# txb0108.net
KiCad netlist of a schematic drawn in EAGLE
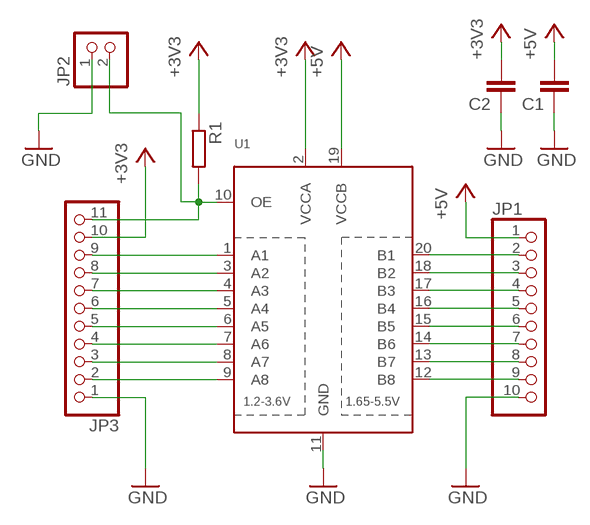
[diagram p0: schematic, sheet 1]

(export (version "E")
  (design (tool "Eeschema 10.0.6"))
  (components
    (comp (ref "C1")
      (value "C-EUC0805K")
      (footprint "eagle-import:C0805K")
      (libsource (lib "eagle-import") (part "C-EUC0805K"))
    )
    (comp (ref "C2")
      (value "C-EUC1206")
      (footprint "eagle-import:C1206")
      (libsource (lib "eagle-import") (part "C-EUC1206"))
    )
    (comp (ref "JP1")
      (value "PINHD-1X10")
      (footprint "eagle-import:1X10")
      (libsource (lib "eagle-import") (part "PINHD-1X10"))
    )
    (comp (ref "JP2")
      (value "PINHD-1X2")
      (footprint "eagle-import:1X02")
      (libsource (lib "eagle-import") (part "PINHD-1X2"))
    )
    (comp (ref "JP3")
      (value "PINHD-1X11")
      (footprint "eagle-import:1X11")
      (libsource (lib "eagle-import") (part "PINHD-1X11"))
    )
    (comp (ref "R1")
      (value "R-EU_M0805")
      (footprint "eagle-import:M0805")
      (libsource (lib "eagle-import") (part "R-EU_M0805"))
    )
    (comp (ref "U1")
      (value "TXB0108PWR")
      (footprint "eagle-import:TSSOP20")
      (libsource (lib "eagle-import") (part "TXB0108PWR"))
    )
  )
  (nets
    (net (code "1") (name "+3V3") (class "Default")
      (node (ref "C2") (pin "2") (pinfunction "2_2") (pintype "passive"))
      (node (ref "JP3") (pin "10") (pinfunction "10_10") (pintype "passive"))
      (node (ref "R1") (pin "1") (pinfunction "1_1") (pintype "passive"))
      (node (ref "U1") (pin "2") (pinfunction "VCCA_2") (pintype "bidirectional"))
    )
    (net (code "2") (name "+5V") (class "Default")
      (node (ref "C1") (pin "2") (pinfunction "2_2") (pintype "passive"))
      (node (ref "JP1") (pin "1") (pinfunction "1_1") (pintype "passive"))
      (node (ref "U1") (pin "19") (pinfunction "VCCB_19") (pintype "bidirectional"))
    )
    (net (code "3") (name "GND") (class "Default")
      (node (ref "C1") (pin "1") (pinfunction "1_1") (pintype "passive"))
      (node (ref "C2") (pin "1") (pinfunction "1_1") (pintype "passive"))
      (node (ref "JP1") (pin "10") (pinfunction "10_10") (pintype "passive"))
      (node (ref "JP2") (pin "1") (pinfunction "1_1") (pintype "passive"))
      (node (ref "JP3") (pin "1") (pinfunction "1_1") (pintype "passive"))
      (node (ref "U1") (pin "11") (pinfunction "GND_11") (pintype "bidirectional"))
    )
    (net (code "4") (name "Net-(U1-A1)") (class "Default")
      (node (ref "JP3") (pin "9") (pinfunction "9_9") (pintype "passive"))
      (node (ref "U1") (pin "1") (pinfunction "A1_1") (pintype "bidirectional"))
    )
    (net (code "5") (name "Net-(U1-A2)") (class "Default")
      (node (ref "JP3") (pin "8") (pinfunction "8_8") (pintype "passive"))
      (node (ref "U1") (pin "3") (pinfunction "A2_3") (pintype "bidirectional"))
    )
    (net (code "6") (name "Net-(U1-A3)") (class "Default")
      (node (ref "JP3") (pin "7") (pinfunction "7_7") (pintype "passive"))
      (node (ref "U1") (pin "4") (pinfunction "A3_4") (pintype "bidirectional"))
    )
    (net (code "7") (name "Net-(U1-A4)") (class "Default")
      (node (ref "JP3") (pin "6") (pinfunction "6_6") (pintype "passive"))
      (node (ref "U1") (pin "5") (pinfunction "A4_5") (pintype "bidirectional"))
    )
    (net (code "8") (name "Net-(U1-A5)") (class "Default")
      (node (ref "JP3") (pin "5") (pinfunction "5_5") (pintype "passive"))
      (node (ref "U1") (pin "6") (pinfunction "A5_6") (pintype "bidirectional"))
    )
    (net (code "9") (name "Net-(U1-A6)") (class "Default")
      (node (ref "JP3") (pin "4") (pinfunction "4_4") (pintype "passive"))
      (node (ref "U1") (pin "7") (pinfunction "A6_7") (pintype "bidirectional"))
    )
    (net (code "10") (name "Net-(U1-A7)") (class "Default")
      (node (ref "JP3") (pin "3") (pinfunction "3_3") (pintype "passive"))
      (node (ref "U1") (pin "8") (pinfunction "A7_8") (pintype "bidirectional"))
    )
    (net (code "11") (name "Net-(U1-A8)") (class "Default")
      (node (ref "JP3") (pin "2") (pinfunction "2_2") (pintype "passive"))
      (node (ref "U1") (pin "9") (pinfunction "A8_9") (pintype "bidirectional"))
    )
    (net (code "12") (name "Net-(U1-B1)") (class "Default")
      (node (ref "JP1") (pin "2") (pinfunction "2_2") (pintype "passive"))
      (node (ref "U1") (pin "20") (pinfunction "B1_20") (pintype "bidirectional"))
    )
    (net (code "13") (name "Net-(U1-B2)") (class "Default")
      (node (ref "JP1") (pin "3") (pinfunction "3_3") (pintype "passive"))
      (node (ref "U1") (pin "18") (pinfunction "B2_18") (pintype "bidirectional"))
    )
    (net (code "14") (name "Net-(U1-B3)") (class "Default")
      (node (ref "JP1") (pin "4") (pinfunction "4_4") (pintype "passive"))
      (node (ref "U1") (pin "17") (pinfunction "B3_17") (pintype "bidirectional"))
    )
    (net (code "15") (name "Net-(U1-B4)") (class "Default")
      (node (ref "JP1") (pin "5") (pinfunction "5_5") (pintype "passive"))
      (node (ref "U1") (pin "16") (pinfunction "B4_16") (pintype "bidirectional"))
    )
    (net (code "16") (name "Net-(U1-B5)") (class "Default")
      (node (ref "JP1") (pin "6") (pinfunction "6_6") (pintype "passive"))
      (node (ref "U1") (pin "15") (pinfunction "B5_15") (pintype "bidirectional"))
    )
    (net (code "17") (name "Net-(U1-B6)") (class "Default")
      (node (ref "JP1") (pin "7") (pinfunction "7_7") (pintype "passive"))
      (node (ref "U1") (pin "14") (pinfunction "B6_14") (pintype "bidirectional"))
    )
    (net (code "18") (name "Net-(U1-B7)") (class "Default")
      (node (ref "JP1") (pin "8") (pinfunction "8_8") (pintype "passive"))
      (node (ref "U1") (pin "13") (pinfunction "B7_13") (pintype "bidirectional"))
    )
    (net (code "19") (name "Net-(U1-B8)") (class "Default")
      (node (ref "JP1") (pin "9") (pinfunction "9_9") (pintype "passive"))
      (node (ref "U1") (pin "12") (pinfunction "B8_12") (pintype "bidirectional"))
    )
    (net (code "20") (name "Net-(U1-OE)") (class "Default")
      (node (ref "JP2") (pin "2") (pinfunction "2_2") (pintype "passive"))
      (node (ref "JP3") (pin "11") (pinfunction "11_11") (pintype "passive"))
      (node (ref "R1") (pin "2") (pinfunction "2_2") (pintype "passive"))
      (node (ref "U1") (pin "10") (pinfunction "OE_10") (pintype "bidirectional"))
    )
  )
)
